# custom-arduino.net
KiCad netlist of a schematic drawn in EAGLE
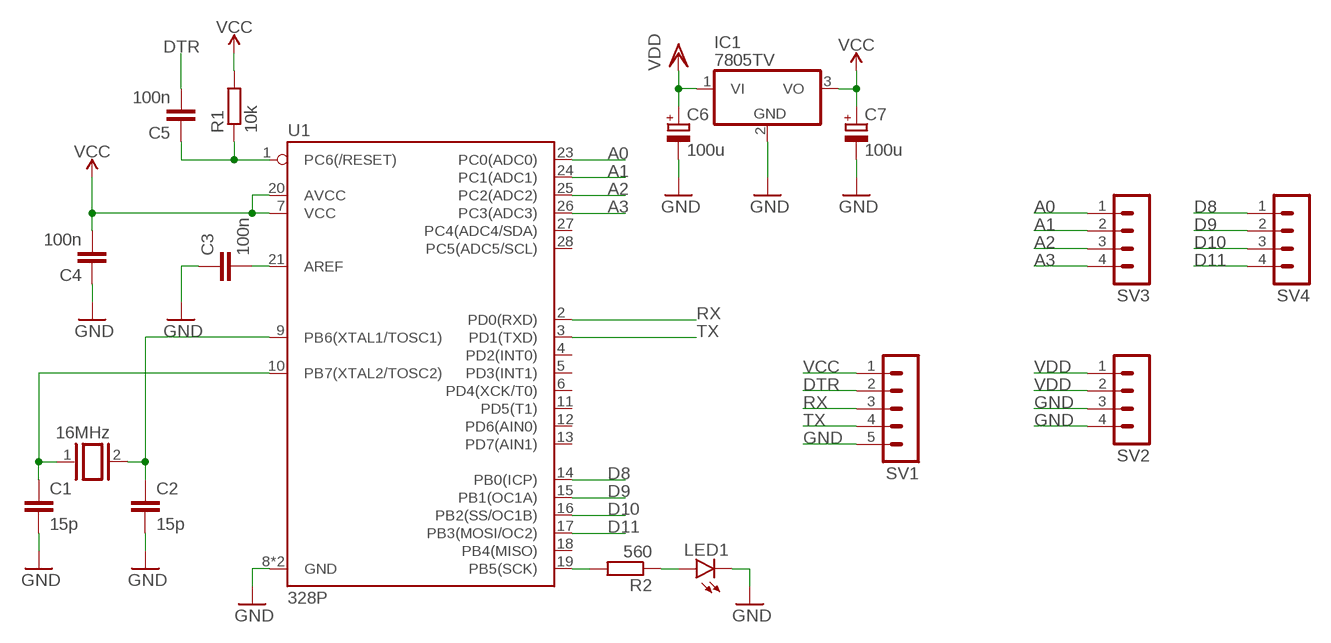
[diagram p0: schematic, sheet 1]

(export (version "E")
  (design (tool "Eeschema 10.0.6"))
  (components
    (comp (ref "C1")
      (value "15p")
      (footprint "eagle-import:C025-024X044")
      (libsource (lib "eagle-import") (part "C-EU025-024X044"))
    )
    (comp (ref "C2")
      (value "15p")
      (footprint "eagle-import:C025-024X044")
      (libsource (lib "eagle-import") (part "C-EU025-024X044"))
    )
    (comp (ref "C3")
      (value "100n")
      (footprint "eagle-import:C025-024X044")
      (libsource (lib "eagle-import") (part "C-EU025-024X044"))
    )
    (comp (ref "C4")
      (value "100n")
      (footprint "eagle-import:C025-024X044")
      (libsource (lib "eagle-import") (part "C-EU025-024X044"))
    )
    (comp (ref "C5")
      (value "100n")
      (footprint "eagle-import:C025-024X044")
      (libsource (lib "eagle-import") (part "C-EU025-024X044"))
    )
    (comp (ref "C6")
      (value "100u")
      (footprint "eagle-import:E2,5-7")
      (libsource (lib "eagle-import") (part "CPOL-EUE2.5-7"))
    )
    (comp (ref "C7")
      (value "100u")
      (footprint "eagle-import:E2,5-7")
      (libsource (lib "eagle-import") (part "CPOL-EUE2.5-7"))
    )
    (comp (ref "IC1")
      (value "7805TV")
      (footprint "eagle-import:TO220V")
      (libsource (lib "eagle-import") (part "78TV05"))
    )
    (comp (ref "LED1")
      (value "LED5MM")
      (footprint "eagle-import:LED5MM")
      (libsource (lib "eagle-import") (part "LED5MM"))
    )
    (comp (ref "Q1")
      (value "16MHz")
      (footprint "eagle-import:QS")
      (libsource (lib "eagle-import") (part "XTAL/S"))
    )
    (comp (ref "R1")
      (value "10k")
      (footprint "eagle-import:0207_10")
      (libsource (lib "eagle-import") (part "R-EU_0207/10"))
    )
    (comp (ref "R2")
      (value "560")
      (footprint "eagle-import:0207_10")
      (libsource (lib "eagle-import") (part "R-EU_0207/10"))
    )
    (comp (ref "SV1")
      (value "MA05-1")
      (footprint "eagle-import:MA05-1")
      (libsource (lib "eagle-import") (part "MA05-1"))
    )
    (comp (ref "SV2")
      (value "MA04-1")
      (footprint "eagle-import:MA04-1")
      (libsource (lib "eagle-import") (part "MA04-1"))
    )
    (comp (ref "SV3")
      (value "MA04-1")
      (footprint "eagle-import:MA04-1")
      (libsource (lib "eagle-import") (part "MA04-1"))
    )
    (comp (ref "SV4")
      (value "MA04-1")
      (footprint "eagle-import:MA04-1")
      (libsource (lib "eagle-import") (part "MA04-1"))
    )
    (comp (ref "U1")
      (value "328P")
      (footprint "eagle-import:DIP28")
      (libsource (lib "eagle-import") (part "ATMEGA328P_PDIP"))
    )
  )
  (nets
    (net (code "1") (name "/A0") (class "Default")
      (node (ref "SV3") (pin "1") (pinfunction "1_1") (pintype "passive"))
      (node (ref "U1") (pin "23") (pinfunction "PC0(ADC0)_23") (pintype "bidirectional"))
    )
    (net (code "2") (name "/A1") (class "Default")
      (node (ref "SV3") (pin "2") (pinfunction "2_2") (pintype "passive"))
      (node (ref "U1") (pin "24") (pinfunction "PC1(ADC1)_24") (pintype "bidirectional"))
    )
    (net (code "3") (name "/A2") (class "Default")
      (node (ref "SV3") (pin "3") (pinfunction "3_3") (pintype "passive"))
      (node (ref "U1") (pin "25") (pinfunction "PC2(ADC2)_25") (pintype "bidirectional"))
    )
    (net (code "4") (name "/A3") (class "Default")
      (node (ref "SV3") (pin "4") (pinfunction "4_4") (pintype "passive"))
      (node (ref "U1") (pin "26") (pinfunction "PC3(ADC3)_26") (pintype "bidirectional"))
    )
    (net (code "5") (name "/D8") (class "Default")
      (node (ref "SV4") (pin "1") (pinfunction "1_1") (pintype "passive"))
      (node (ref "U1") (pin "14") (pinfunction "PB0(ICP)_14") (pintype "bidirectional"))
    )
    (net (code "6") (name "/D9") (class "Default")
      (node (ref "SV4") (pin "2") (pinfunction "2_2") (pintype "passive"))
      (node (ref "U1") (pin "15") (pinfunction "PB1(OC1A)_15") (pintype "bidirectional"))
    )
    (net (code "7") (name "/D10") (class "Default")
      (node (ref "SV4") (pin "3") (pinfunction "3_3") (pintype "passive"))
      (node (ref "U1") (pin "16") (pinfunction "PB2(SS/OC1B)_16") (pintype "bidirectional"))
    )
    (net (code "8") (name "/D11") (class "Default")
      (node (ref "SV4") (pin "4") (pinfunction "4_4") (pintype "passive"))
      (node (ref "U1") (pin "17") (pinfunction "PB3(MOSI/OC2)_17") (pintype "bidirectional"))
    )
    (net (code "9") (name "/DTR") (class "Default")
      (node (ref "C5") (pin "2") (pinfunction "2_2") (pintype "passive"))
      (node (ref "SV1") (pin "2") (pinfunction "2_2") (pintype "passive"))
    )
    (net (code "10") (name "/RX") (class "Default")
      (node (ref "SV1") (pin "3") (pinfunction "3_3") (pintype "passive"))
      (node (ref "U1") (pin "2") (pinfunction "PD0(RXD)_2") (pintype "bidirectional"))
    )
    (net (code "11") (name "/TX") (class "Default")
      (node (ref "SV1") (pin "4") (pinfunction "4_4") (pintype "passive"))
      (node (ref "U1") (pin "3") (pinfunction "PD1(TXD)_3") (pintype "bidirectional"))
    )
    (net (code "12") (name "GND") (class "Default")
      (node (ref "C1") (pin "2") (pinfunction "2_2") (pintype "passive"))
      (node (ref "C2") (pin "2") (pinfunction "2_2") (pintype "passive"))
      (node (ref "C3") (pin "1") (pinfunction "1_1") (pintype "passive"))
      (node (ref "C4") (pin "1") (pinfunction "1_1") (pintype "passive"))
      (node (ref "C6") (pin "-") (pinfunction "-_-") (pintype "passive"))
      (node (ref "C7") (pin "-") (pinfunction "-_-") (pintype "passive"))
      (node (ref "IC1") (pin "2") (pinfunction "GND_2") (pintype "passive"))
      (node (ref "LED1") (pin "K") (pinfunction "C_K") (pintype "passive"))
      (node (ref "SV1") (pin "5") (pinfunction "5_5") (pintype "passive"))
      (node (ref "SV2") (pin "3") (pinfunction "3_3") (pintype "passive"))
      (node (ref "SV2") (pin "4") (pinfunction "4_4") (pintype "passive"))
      (node (ref "U1") (pin "22") (pinfunction "GND_22") (pintype "bidirectional"))
      (node (ref "U1") (pin "8") (pinfunction "GND_8") (pintype "bidirectional"))
    )
    (net (code "13") (name "Net-(LED1-PadA)") (class "Default")
      (node (ref "LED1") (pin "A") (pinfunction "A_A") (pintype "passive"))
      (node (ref "R2") (pin "1") (pinfunction "1_1") (pintype "passive"))
    )
    (net (code "14") (name "Net-(U1-AREF)") (class "Default")
      (node (ref "C3") (pin "2") (pinfunction "2_2") (pintype "passive"))
      (node (ref "U1") (pin "21") (pinfunction "AREF_21") (pintype "bidirectional"))
    )
    (net (code "15") (name "Net-(U1-PB5(SCK))") (class "Default")
      (node (ref "R2") (pin "2") (pinfunction "2_2") (pintype "passive"))
      (node (ref "U1") (pin "19") (pinfunction "PB5(SCK)_19") (pintype "bidirectional"))
    )
    (net (code "16") (name "Net-(U1-PB6(XTAL1{slash}TOSC1))") (class "Default")
      (node (ref "C2") (pin "1") (pinfunction "1_1") (pintype "passive"))
      (node (ref "Q1") (pin "2") (pinfunction "2_2") (pintype "passive"))
      (node (ref "U1") (pin "9") (pinfunction "PB6(XTAL1/TOSC1)_9") (pintype "bidirectional"))
    )
    (net (code "17") (name "Net-(U1-PB7(XTAL2{slash}TOSC2))") (class "Default")
      (node (ref "C1") (pin "1") (pinfunction "1_1") (pintype "passive"))
      (node (ref "Q1") (pin "1") (pinfunction "1_1") (pintype "passive"))
      (node (ref "U1") (pin "10") (pinfunction "PB7(XTAL2/TOSC2)_10") (pintype "bidirectional"))
    )
    (net (code "18") (name "Net-(U1-PC6({slash}RESET))") (class "Default")
      (node (ref "C5") (pin "1") (pinfunction "1_1") (pintype "passive"))
      (node (ref "R1") (pin "1") (pinfunction "1_1") (pintype "passive"))
      (node (ref "U1") (pin "1") (pinfunction "PC6(/RESET)_1") (pintype "bidirectional"))
    )
    (net (code "19") (name "VCC") (class "Default")
      (node (ref "C4") (pin "2") (pinfunction "2_2") (pintype "passive"))
      (node (ref "C7") (pin "+") (pinfunction "+_+") (pintype "passive"))
      (node (ref "IC1") (pin "3") (pinfunction "VO_3") (pintype "passive"))
      (node (ref "R1") (pin "2") (pinfunction "2_2") (pintype "passive"))
      (node (ref "SV1") (pin "1") (pinfunction "1_1") (pintype "passive"))
      (node (ref "U1") (pin "20") (pinfunction "AVCC_20") (pintype "bidirectional"))
      (node (ref "U1") (pin "7") (pinfunction "VCC_7") (pintype "bidirectional"))
    )
    (net (code "20") (name "VDD") (class "Default")
      (node (ref "C6") (pin "+") (pinfunction "+_+") (pintype "passive"))
      (node (ref "IC1") (pin "1") (pinfunction "VI_1") (pintype "input"))
      (node (ref "SV2") (pin "1") (pinfunction "1_1") (pintype "passive"))
      (node (ref "SV2") (pin "2") (pinfunction "2_2") (pintype "passive"))
    )
    (net (code "21") (name "unconnected-(U1-PB4(MISO)-Pad18)") (class "Default")
      (node (ref "U1") (pin "18") (pinfunction "PB4(MISO)_18") (pintype "bidirectional"))
    )
    (net (code "22") (name "unconnected-(U1-PC4(ADC4{slash}SDA)-Pad27)") (class "Default")
      (node (ref "U1") (pin "27") (pinfunction "PC4(ADC4/SDA)_27") (pintype "bidirectional"))
    )
    (net (code "23") (name "unconnected-(U1-PC5(ADC5{slash}SCL)-Pad28)") (class "Default")
      (node (ref "U1") (pin "28") (pinfunction "PC5(ADC5/SCL)_28") (pintype "bidirectional"))
    )
    (net (code "24") (name "unconnected-(U1-PD2(INT0)-Pad4)") (class "Default")
      (node (ref "U1") (pin "4") (pinfunction "PD2(INT0)_4") (pintype "bidirectional"))
    )
    (net (code "25") (name "unconnected-(U1-PD3(INT1)-Pad5)") (class "Default")
      (node (ref "U1") (pin "5") (pinfunction "PD3(INT1)_5") (pintype "bidirectional"))
    )
    (net (code "26") (name "unconnected-(U1-PD4(XCK{slash}T0)-Pad6)") (class "Default")
      (node (ref "U1") (pin "6") (pinfunction "PD4(XCK/T0)_6") (pintype "bidirectional"))
    )
    (net (code "27") (name "unconnected-(U1-PD5(T1)-Pad11)") (class "Default")
      (node (ref "U1") (pin "11") (pinfunction "PD5(T1)_11") (pintype "bidirectional"))
    )
    (net (code "28") (name "unconnected-(U1-PD6(AIN0)-Pad12)") (class "Default")
      (node (ref "U1") (pin "12") (pinfunction "PD6(AIN0)_12") (pintype "bidirectional"))
    )
    (net (code "29") (name "unconnected-(U1-PD7(AIN1)-Pad13)") (class "Default")
      (node (ref "U1") (pin "13") (pinfunction "PD7(AIN1)_13") (pintype "bidirectional"))
    )
  )
)
